# untitled.net
KiCad netlist of a schematic drawn in EAGLE
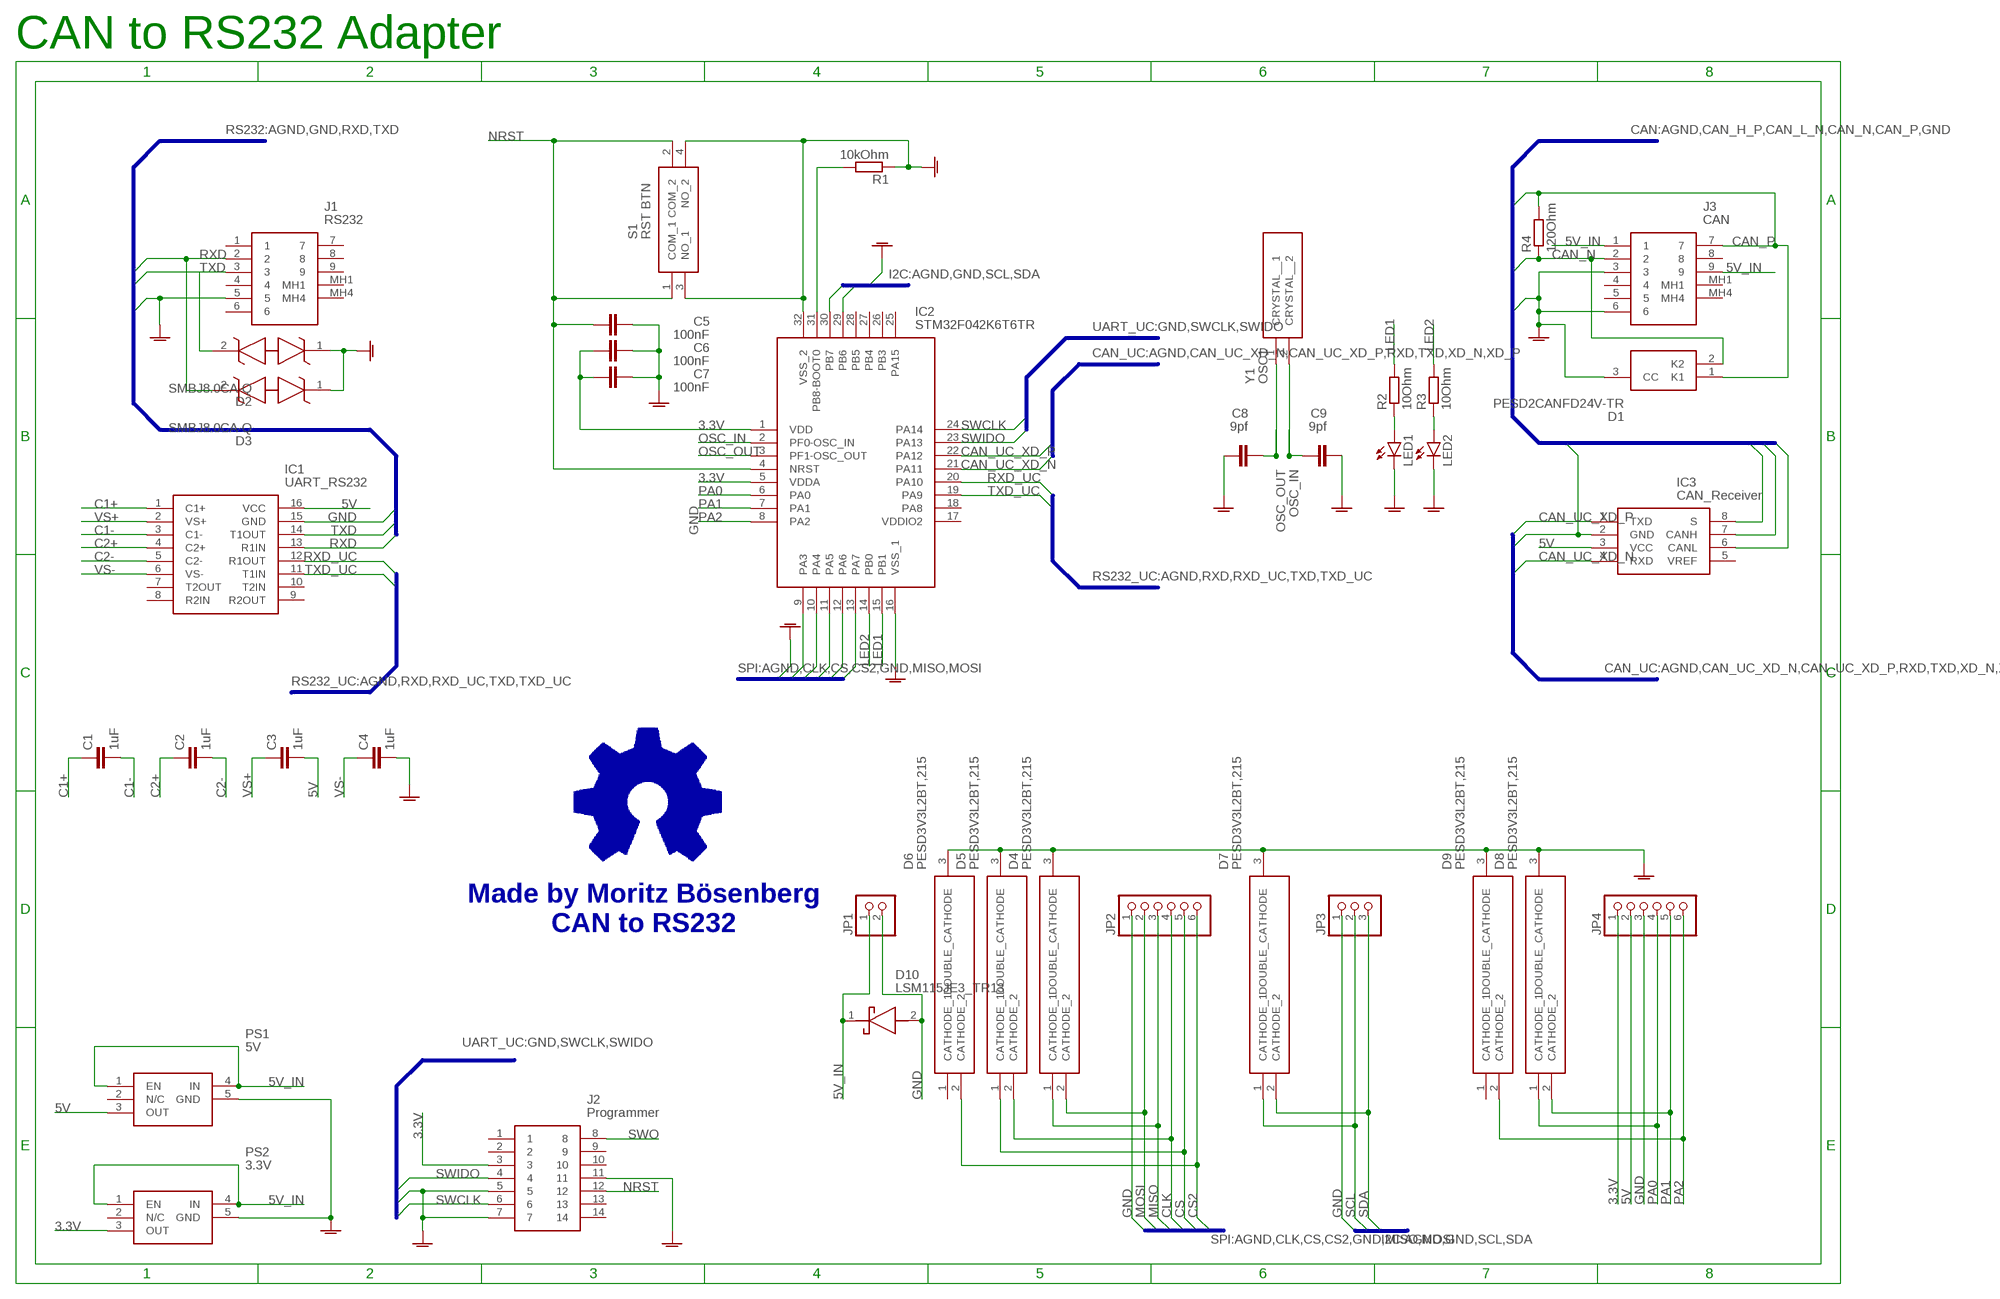
[diagram p0: schematic, sheet 1]

(export (version "E")
  (design (tool "Eeschema 10.0.6"))
  (components
    (comp (ref "C1")
      (value "1uF")
      (footprint "eagle-import:C0805")
      (libsource (lib "eagle-import") (part "C-EU_805C0805"))
    )
    (comp (ref "C2")
      (value "1uF")
      (footprint "eagle-import:C0805")
      (libsource (lib "eagle-import") (part "C-EU_805C0805"))
    )
    (comp (ref "C3")
      (value "1uF")
      (footprint "eagle-import:C0805")
      (libsource (lib "eagle-import") (part "C-EU_805C0805"))
    )
    (comp (ref "C4")
      (value "1uF")
      (footprint "eagle-import:C0805")
      (libsource (lib "eagle-import") (part "C-EU_805C0805"))
    )
    (comp (ref "C5")
      (value "100nF")
      (footprint "eagle-import:C0805")
      (libsource (lib "eagle-import") (part "C-EU_805C0805"))
    )
    (comp (ref "C6")
      (value "100nF")
      (footprint "eagle-import:C0805")
      (libsource (lib "eagle-import") (part "C-EU_805C0805"))
    )
    (comp (ref "C7")
      (value "100nF")
      (footprint "eagle-import:C0805")
      (libsource (lib "eagle-import") (part "C-EU_805C0805"))
    )
    (comp (ref "C8")
      (value "9pf")
      (footprint "eagle-import:C0805")
      (libsource (lib "eagle-import") (part "C-EU_805C0805"))
    )
    (comp (ref "C9")
      (value "9pf")
      (footprint "eagle-import:C0805")
      (libsource (lib "eagle-import") (part "C-EU_805C0805"))
    )
    (comp (ref "D1")
      (value "PESD2CANFD24V-TR")
      (footprint "eagle-import:SOT95P230X110-3N")
      (fields (field (name "MOUSER_PART_NUMBER") "771-PESD2CANFD24V-TR"))
      (libsource (lib "eagle-import") (part "PESD2CANFD24V-TR"))
    )
    (comp (ref "D2")
      (value "SMBJ8.0CA-Q")
      (footprint "eagle-import:DIONM5436X244N")
      (fields (field (name "MOUSER_PART_NUMBER") "652-SMBJ8.0CA-Q"))
      (libsource (lib "eagle-import") (part "SMBJ8.0CA-Q"))
    )
    (comp (ref "D3")
      (value "SMBJ8.0CA-Q")
      (footprint "eagle-import:DIONM5436X244N")
      (fields (field (name "MOUSER_PART_NUMBER") "652-SMBJ8.0CA-Q"))
      (libsource (lib "eagle-import") (part "SMBJ8.0CA-Q"))
    )
    (comp (ref "D4")
      (value "PESD3V3L2BT,215")
      (footprint "eagle-import:SOT95P230X110-3N")
      (fields (field (name "MOUSER_PART_NUMBER") "771-PESD3V3L2BT-T/R"))
      (libsource (lib "eagle-import") (part "PESD3V3L2BT,215"))
    )
    (comp (ref "D5")
      (value "PESD3V3L2BT,215")
      (footprint "eagle-import:SOT95P230X110-3N")
      (fields (field (name "MOUSER_PART_NUMBER") "771-PESD3V3L2BT-T/R"))
      (libsource (lib "eagle-import") (part "PESD3V3L2BT,215"))
    )
    (comp (ref "D6")
      (value "PESD3V3L2BT,215")
      (footprint "eagle-import:SOT95P230X110-3N")
      (fields (field (name "MOUSER_PART_NUMBER") "771-PESD3V3L2BT-T/R"))
      (libsource (lib "eagle-import") (part "PESD3V3L2BT,215"))
    )
    (comp (ref "D7")
      (value "PESD3V3L2BT,215")
      (footprint "eagle-import:SOT95P230X110-3N")
      (fields (field (name "MOUSER_PART_NUMBER") "771-PESD3V3L2BT-T/R"))
      (libsource (lib "eagle-import") (part "PESD3V3L2BT,215"))
    )
    (comp (ref "D8")
      (value "PESD3V3L2BT,215")
      (footprint "eagle-import:SOT95P230X110-3N")
      (fields (field (name "MOUSER_PART_NUMBER") "771-PESD3V3L2BT-T/R"))
      (libsource (lib "eagle-import") (part "PESD3V3L2BT,215"))
    )
    (comp (ref "D9")
      (value "PESD3V3L2BT,215")
      (footprint "eagle-import:SOT95P230X110-3N")
      (fields (field (name "MOUSER_PART_NUMBER") "771-PESD3V3L2BT-T/R"))
      (libsource (lib "eagle-import") (part "PESD3V3L2BT,215"))
    )
    (comp (ref "D10")
      (value "LSM115JE3_TR13")
      (footprint "eagle-import:DIOM5436X330N")
      (fields
        (field (name "MANUFACTURER_PART_NUMBER") "LSM115JE3/TR13")
        (field (name "MOUSER_PART_NUMBER") "494-LSM115JE3/TR13")
      )
      (libsource (lib "eagle-import") (part "LSM115JE3_TR13"))
    )
    (comp (ref "IC1")
      (value "UART_RS232")
      (footprint "eagle-import:SOIC127P600X175-16N")
      (fields
        (field (name "MANUFACTURER_PART_NUMBER") "MAX232DRG4")
        (field (name "MOUSER_PART_NUMBER") "595-MAX232DRG4")
      )
      (libsource (lib "eagle-import") (part "MAX232DRG4"))
    )
    (comp (ref "IC2")
      (value "STM32F042K6T6TR")
      (footprint "eagle-import:QFP80P900X900X160-32N")
      (fields (field (name "MOUSER_PART_NUMBER") "511-STM32F042K6T6TR"))
      (libsource (lib "eagle-import") (part "STM32F042K6T6TR"))
    )
    (comp (ref "IC3")
      (value "CAN_Receiver")
      (footprint "eagle-import:SOIC127P600X175-8N")
      (fields
        (field (name "MANUFACTURER_PART_NUMBER") "TJA1050T/CM,118")
        (field (name "MOUSER_PART_NUMBER") "771-TJA1050T/CM118")
      )
      (libsource (lib "eagle-import") (part "TJA1050T_CM,118"))
    )
    (comp (ref "J1")
      (value "RS232")
      (footprint "eagle-import:K202XHTE9SN")
      (fields
        (field (name "MANUFACTURER_PART_NUMBER") "K202XHT-E9S-N")
        (field (name "MOUSER_PART_NUMBER") "806-K202XHT-E9S-N")
      )
      (libsource (lib "eagle-import") (part "K202XHT-E9S-N"))
    )
    (comp (ref "J2")
      (value "Programmer")
      (footprint "eagle-import:FTSH10701LDVKA")
      (fields
        (field (name "MANUFACTURER_PART_NUMBER") "FTSH-107-01-L-DV-K-A")
        (field (name "MOUSER_PART_NUMBER") "200-FTSH10701LDVKA")
      )
      (libsource (lib "eagle-import") (part "FTSH-107-01-L-DV-K-A"))
    )
    (comp (ref "J3")
      (value "CAN")
      (footprint "eagle-import:K202XHTE9SN")
      (fields
        (field (name "MANUFACTURER_PART_NUMBER") "K202XHT-E9S-N")
        (field (name "MOUSER_PART_NUMBER") "806-K202XHT-E9S-N")
      )
      (libsource (lib "eagle-import") (part "K202XHT-E9S-N"))
    )
    (comp (ref "JP1")
      (value "PINHD-1X2")
      (footprint "eagle-import:1X02")
      (libsource (lib "eagle-import") (part "PINHD-1X2"))
    )
    (comp (ref "JP2")
      (value "PINHD-1X6")
      (footprint "eagle-import:1X06")
      (libsource (lib "eagle-import") (part "PINHD-1X6"))
    )
    (comp (ref "JP3")
      (value "PINHD-1X3")
      (footprint "eagle-import:1X03")
      (libsource (lib "eagle-import") (part "PINHD-1X3"))
    )
    (comp (ref "JP4")
      (value "PINHD-1X6")
      (footprint "eagle-import:1X06")
      (libsource (lib "eagle-import") (part "PINHD-1X6"))
    )
    (comp (ref "LED1")
      (value "LED_805SML0805")
      (footprint "eagle-import:SML0805")
      (libsource (lib "eagle-import") (part "LED_805SML0805"))
    )
    (comp (ref "LED2")
      (value "LED_805SML0805")
      (footprint "eagle-import:SML0805")
      (libsource (lib "eagle-import") (part "LED_805SML0805"))
    )
    (comp (ref "PS1")
      (value "5V")
      (footprint "eagle-import:SOT150P700X160-5N")
      (libsource (lib "eagle-import") (part "LP38693MPX-5.0_NOPB"))
    )
    (comp (ref "PS2")
      (value "3.3V")
      (footprint "eagle-import:SOT150P700X160-5N")
      (libsource (lib "eagle-import") (part "LP38693MPX-5.0_NOPB"))
    )
    (comp (ref "R1")
      (value "10kOhm")
      (footprint "eagle-import:R0805")
      (libsource (lib "eagle-import") (part "R-EU_805R0805"))
    )
    (comp (ref "R2")
      (value "10Ohm")
      (footprint "eagle-import:R0805")
      (libsource (lib "eagle-import") (part "R-EU_805R0805"))
    )
    (comp (ref "R3")
      (value "10Ohm")
      (footprint "eagle-import:R0805")
      (libsource (lib "eagle-import") (part "R-EU_805R0805"))
    )
    (comp (ref "R4")
      (value "120Ohm")
      (footprint "eagle-import:R0805")
      (libsource (lib "eagle-import") (part "R-EU_805R0805"))
    )
    (comp (ref "S1")
      (value "RST BTN")
      (footprint "eagle-import:PTS526SM15SMTR2LFS")
      (fields
        (field (name "MANUFACTURER_PART_NUMBER") "PTS526 SM15 SMTR2 LFS")
        (field (name "MOUSER_PART_NUMBER") "611-PTS526SM15SMTR2L")
      )
      (libsource (lib "eagle-import") (part "PTS526_SM15_SMTR2_LFS"))
    )
    (comp (ref "Y1")
      (value "OSC1")
      (footprint "eagle-import:CM7VT1A32768KHZ7PF100PPMTAQC")
      (fields
        (field (name "MANUFACTURER_PART_NUMBER") "CM7V-T1A-32.768KHZ-7PF-100PPM-TA-QC")
        (field (name "MOUSER_PART_NUMBER") "428-202156-MG01")
      )
      (libsource (lib "eagle-import") (part "CM7V-T1A-32.768KHZ-7PF-100PPM-"))
    )
  )
  (nets
    (net (code "12") (name "/3.3V") (class "Default")
      (node (ref "C6") (pin "1") (pinfunction "1_1") (pintype "passive"))
      (node (ref "C7") (pin "1") (pinfunction "1_1") (pintype "passive"))
      (node (ref "IC2") (pin "1") (pinfunction "VDD_1") (pintype "bidirectional"))
      (node (ref "IC2") (pin "5") (pinfunction "VDDA_5") (pintype "bidirectional"))
      (node (ref "J2") (pin "3") (pinfunction "3_3") (pintype "bidirectional"))
      (node (ref "JP4") (pin "1") (pinfunction "1_1") (pintype "passive"))
      (node (ref "PS2") (pin "3") (pinfunction "OUT_3") (pintype "bidirectional"))
    )
    (net (code "13") (name "/5V") (class "Default")
      (node (ref "C3") (pin "2") (pinfunction "2_2") (pintype "passive"))
      (node (ref "IC1") (pin "16") (pinfunction "VCC_16") (pintype "bidirectional"))
      (node (ref "IC3") (pin "3") (pinfunction "VCC_3") (pintype "bidirectional"))
      (node (ref "JP4") (pin "2") (pinfunction "2_2") (pintype "passive"))
      (node (ref "PS1") (pin "3") (pinfunction "OUT_3") (pintype "bidirectional"))
    )
    (net (code "14") (name "/5V_IN") (class "Default")
      (node (ref "D10") (pin "1") (pinfunction "K_1") (pintype "bidirectional"))
      (node (ref "J3") (pin "1") (pinfunction "1_1") (pintype "bidirectional"))
      (node (ref "J3") (pin "9") (pinfunction "9_9") (pintype "bidirectional"))
      (node (ref "JP1") (pin "1") (pinfunction "1_1") (pintype "passive"))
      (node (ref "PS1") (pin "1") (pinfunction "EN_1") (pintype "bidirectional"))
      (node (ref "PS1") (pin "4") (pinfunction "IN_4") (pintype "bidirectional"))
      (node (ref "PS2") (pin "1") (pinfunction "EN_1") (pintype "bidirectional"))
      (node (ref "PS2") (pin "4") (pinfunction "IN_4") (pintype "bidirectional"))
    )
    (net (code "15") (name "/C1+") (class "Default")
      (node (ref "C1") (pin "1") (pinfunction "1_1") (pintype "passive"))
      (node (ref "IC1") (pin "1") (pinfunction "C1+_1") (pintype "bidirectional"))
    )
    (net (code "16") (name "/C1-") (class "Default")
      (node (ref "C1") (pin "2") (pinfunction "2_2") (pintype "passive"))
      (node (ref "IC1") (pin "3") (pinfunction "C1-_3") (pintype "bidirectional"))
    )
    (net (code "17") (name "/C2+") (class "Default")
      (node (ref "C2") (pin "1") (pinfunction "1_1") (pintype "passive"))
      (node (ref "IC1") (pin "4") (pinfunction "C2+_4") (pintype "bidirectional"))
    )
    (net (code "18") (name "/C2-") (class "Default")
      (node (ref "C2") (pin "2") (pinfunction "2_2") (pintype "passive"))
      (node (ref "IC1") (pin "5") (pinfunction "C2-_5") (pintype "bidirectional"))
    )
    (net (code "19") (name "/CAN_N") (class "Default")
      (node (ref "D1") (pin "2") (pinfunction "K2_2") (pintype "bidirectional"))
      (node (ref "IC3") (pin "6") (pinfunction "CANL_6") (pintype "bidirectional"))
      (node (ref "J3") (pin "2") (pinfunction "2_2") (pintype "bidirectional"))
      (node (ref "R4") (pin "1") (pinfunction "1_1") (pintype "passive"))
    )
    (net (code "20") (name "/CAN_P") (class "Default")
      (node (ref "D1") (pin "1") (pinfunction "K1_1") (pintype "bidirectional"))
      (node (ref "IC3") (pin "7") (pinfunction "CANH_7") (pintype "bidirectional"))
      (node (ref "J3") (pin "7") (pinfunction "7_7") (pintype "bidirectional"))
      (node (ref "R4") (pin "2") (pinfunction "2_2") (pintype "passive"))
    )
    (net (code "21") (name "/CAN_UC_XD_N") (class "Default")
      (node (ref "IC2") (pin "21") (pinfunction "PA11_21") (pintype "bidirectional"))
      (node (ref "IC3") (pin "4") (pinfunction "RXD_4") (pintype "bidirectional"))
    )
    (net (code "22") (name "/CAN_UC_XD_P") (class "Default")
      (node (ref "IC2") (pin "22") (pinfunction "PA12_22") (pintype "bidirectional"))
      (node (ref "IC3") (pin "1") (pinfunction "TXD_1") (pintype "bidirectional"))
    )
    (net (code "23") (name "/CLK") (class "Default")
      (node (ref "D5") (pin "2") (pinfunction "CATHODE_2_2") (pintype "bidirectional"))
      (node (ref "IC2") (pin "11") (pinfunction "PA5_11") (pintype "bidirectional"))
      (node (ref "JP2") (pin "4") (pinfunction "4_4") (pintype "passive"))
    )
    (net (code "24") (name "/CS") (class "Default")
      (node (ref "D5") (pin "1") (pinfunction "CATHODE_1_1") (pintype "bidirectional"))
      (node (ref "IC2") (pin "10") (pinfunction "PA4_10") (pintype "bidirectional"))
      (node (ref "JP2") (pin "5") (pinfunction "5_5") (pintype "passive"))
    )
    (net (code "25") (name "/CS2") (class "Default")
      (node (ref "D6") (pin "2") (pinfunction "CATHODE_2_2") (pintype "bidirectional"))
      (node (ref "IC2") (pin "9") (pinfunction "PA3_9") (pintype "bidirectional"))
      (node (ref "JP2") (pin "6") (pinfunction "6_6") (pintype "passive"))
    )
    (net (code "26") (name "/LED1") (class "Default")
      (node (ref "IC2") (pin "15") (pinfunction "PB1_15") (pintype "bidirectional"))
      (node (ref "R2") (pin "2") (pinfunction "2_2") (pintype "passive"))
    )
    (net (code "27") (name "/LED2") (class "Default")
      (node (ref "IC2") (pin "14") (pinfunction "PB0_14") (pintype "bidirectional"))
      (node (ref "R3") (pin "2") (pinfunction "2_2") (pintype "passive"))
    )
    (net (code "28") (name "/MISO") (class "Default")
      (node (ref "D4") (pin "1") (pinfunction "CATHODE_1_1") (pintype "bidirectional"))
      (node (ref "IC2") (pin "12") (pinfunction "PA6_12") (pintype "bidirectional"))
      (node (ref "JP2") (pin "3") (pinfunction "3_3") (pintype "passive"))
    )
    (net (code "29") (name "/MOSI") (class "Default")
      (node (ref "D4") (pin "2") (pinfunction "CATHODE_2_2") (pintype "bidirectional"))
      (node (ref "IC2") (pin "13") (pinfunction "PA7_13") (pintype "bidirectional"))
      (node (ref "JP2") (pin "2") (pinfunction "2_2") (pintype "passive"))
    )
    (net (code "30") (name "/NRST") (class "Default")
      (node (ref "C5") (pin "1") (pinfunction "1_1") (pintype "passive"))
      (node (ref "IC2") (pin "4") (pinfunction "NRST_4") (pintype "bidirectional"))
      (node (ref "J2") (pin "12") (pinfunction "12_12") (pintype "bidirectional"))
      (node (ref "S1") (pin "1") (pinfunction "COM_1_1") (pintype "bidirectional"))
      (node (ref "S1") (pin "2") (pinfunction "COM_2_2") (pintype "bidirectional"))
    )
    (net (code "31") (name "/OSC_IN") (class "Default")
      (node (ref "C9") (pin "1") (pinfunction "1_1") (pintype "passive"))
      (node (ref "IC2") (pin "2") (pinfunction "PF0-OSC_IN_2") (pintype "bidirectional"))
      (node (ref "Y1") (pin "2") (pinfunction "CRYSTAL__2_2") (pintype "bidirectional"))
    )
    (net (code "32") (name "/OSC_OUT") (class "Default")
      (node (ref "C8") (pin "2") (pinfunction "2_2") (pintype "passive"))
      (node (ref "IC2") (pin "3") (pinfunction "PF1-OSC_OUT_3") (pintype "bidirectional"))
      (node (ref "Y1") (pin "1") (pinfunction "CRYSTAL__1_1") (pintype "bidirectional"))
    )
    (net (code "33") (name "/PA0") (class "Default")
      (node (ref "D8") (pin "1") (pinfunction "CATHODE_1_1") (pintype "bidirectional"))
      (node (ref "IC2") (pin "6") (pinfunction "PA0_6") (pintype "bidirectional"))
      (node (ref "JP4") (pin "4") (pinfunction "4_4") (pintype "passive"))
    )
    (net (code "34") (name "/PA1") (class "Default")
      (node (ref "D8") (pin "2") (pinfunction "CATHODE_2_2") (pintype "bidirectional"))
      (node (ref "IC2") (pin "7") (pinfunction "PA1_7") (pintype "bidirectional"))
      (node (ref "JP4") (pin "5") (pinfunction "5_5") (pintype "passive"))
    )
    (net (code "35") (name "/PA2") (class "Default")
      (node (ref "D9") (pin "2") (pinfunction "CATHODE_2_2") (pintype "bidirectional"))
      (node (ref "IC2") (pin "8") (pinfunction "PA2_8") (pintype "bidirectional"))
      (node (ref "JP4") (pin "6") (pinfunction "6_6") (pintype "passive"))
    )
    (net (code "36") (name "/RXD") (class "Default")
      (node (ref "D3") (pin "2") (pinfunction "2_2") (pintype "bidirectional"))
      (node (ref "IC1") (pin "13") (pinfunction "R1IN_13") (pintype "bidirectional"))
      (node (ref "J1") (pin "2") (pinfunction "2_2") (pintype "bidirectional"))
    )
    (net (code "37") (name "/RXD_UC") (class "Default")
      (node (ref "IC1") (pin "12") (pinfunction "R1OUT_12") (pintype "bidirectional"))
      (node (ref "IC2") (pin "20") (pinfunction "PA10_20") (pintype "bidirectional"))
    )
    (net (code "38") (name "/SCL") (class "Default")
      (node (ref "D7") (pin "1") (pinfunction "CATHODE_1_1") (pintype "bidirectional"))
      (node (ref "IC2") (pin "29") (pinfunction "PB6_29") (pintype "bidirectional"))
      (node (ref "JP3") (pin "2") (pinfunction "2_2") (pintype "passive"))
    )
    (net (code "39") (name "/SDA") (class "Default")
      (node (ref "D7") (pin "2") (pinfunction "CATHODE_2_2") (pintype "bidirectional"))
      (node (ref "IC2") (pin "30") (pinfunction "PB7_30") (pintype "bidirectional"))
      (node (ref "JP3") (pin "3") (pinfunction "3_3") (pintype "passive"))
    )
    (net (code "40") (name "/SWCLK") (class "Default")
      (node (ref "IC2") (pin "24") (pinfunction "PA14_24") (pintype "bidirectional"))
      (node (ref "J2") (pin "6") (pinfunction "6_6") (pintype "bidirectional"))
    )
    (net (code "41") (name "/SWIDO") (class "Default")
      (node (ref "IC2") (pin "23") (pinfunction "PA13_23") (pintype "bidirectional"))
      (node (ref "J2") (pin "4") (pinfunction "4_4") (pintype "bidirectional"))
    )
    (net (code "42") (name "/SWO") (class "Default")
      (node (ref "J2") (pin "8") (pinfunction "8_8") (pintype "bidirectional"))
    )
    (net (code "43") (name "/TXD") (class "Default")
      (node (ref "D2") (pin "2") (pinfunction "2_2") (pintype "bidirectional"))
      (node (ref "IC1") (pin "14") (pinfunction "T1OUT_14") (pintype "bidirectional"))
      (node (ref "J1") (pin "3") (pinfunction "3_3") (pintype "bidirectional"))
    )
    (net (code "44") (name "/TXD_UC") (class "Default")
      (node (ref "IC1") (pin "11") (pinfunction "T1IN_11") (pintype "bidirectional"))
      (node (ref "IC2") (pin "19") (pinfunction "PA9_19") (pintype "bidirectional"))
    )
    (net (code "45") (name "/VS+") (class "Default")
      (node (ref "C3") (pin "1") (pinfunction "1_1") (pintype "passive"))
      (node (ref "IC1") (pin "2") (pinfunction "VS+_2") (pintype "bidirectional"))
    )
    (net (code "46") (name "/VS-") (class "Default")
      (node (ref "C4") (pin "1") (pinfunction "1_1") (pintype "passive"))
      (node (ref "IC1") (pin "6") (pinfunction "VS-_6") (pintype "bidirectional"))
    )
    (net (code "54") (name "GNDA") (class "Default")
      (node (ref "C4") (pin "2") (pinfunction "2_2") (pintype "passive"))
      (node (ref "C5") (pin "2") (pinfunction "2_2") (pintype "passive"))
      (node (ref "C6") (pin "2") (pinfunction "2_2") (pintype "passive"))
      (node (ref "C7") (pin "2") (pinfunction "2_2") (pintype "passive"))
      (node (ref "C8") (pin "1") (pinfunction "1_1") (pintype "passive"))
      (node (ref "C9") (pin "2") (pinfunction "2_2") (pintype "passive"))
      (node (ref "D1") (pin "3") (pinfunction "CC_3") (pintype "bidirectional"))
      (node (ref "D10") (pin "2") (pinfunction "A_2") (pintype "bidirectional"))
      (node (ref "D2") (pin "1") (pinfunction "1_1") (pintype "bidirectional"))
      (node (ref "D3") (pin "1") (pinfunction "1_1") (pintype "bidirectional"))
      (node (ref "D4") (pin "3") (pinfunction "DOUBLE_CATHODE_3") (pintype "bidirectional"))
      (node (ref "D5") (pin "3") (pinfunction "DOUBLE_CATHODE_3") (pintype "bidirectional"))
      (node (ref "D6") (pin "3") (pinfunction "DOUBLE_CATHODE_3") (pintype "bidirectional"))
      (node (ref "D7") (pin "3") (pinfunction "DOUBLE_CATHODE_3") (pintype "bidirectional"))
      (node (ref "D8") (pin "3") (pinfunction "DOUBLE_CATHODE_3") (pintype "bidirectional"))
      (node (ref "D9") (pin "3") (pinfunction "DOUBLE_CATHODE_3") (pintype "bidirectional"))
      (node (ref "IC1") (pin "15") (pinfunction "GND_15") (pintype "bidirectional"))
      (node (ref "IC2") (pin "16") (pinfunction "VSS_1_16") (pintype "bidirectional"))
      (node (ref "IC2") (pin "32") (pinfunction "VSS_2_32") (pintype "bidirectional"))
      (node (ref "IC3") (pin "2") (pinfunction "GND_2") (pintype "bidirectional"))
      (node (ref "IC3") (pin "8") (pinfunction "S_8") (pintype "bidirectional"))
      (node (ref "J1") (pin "5") (pinfunction "5_5") (pintype "bidirectional"))
      (node (ref "J2") (pin "11") (pinfunction "11_11") (pintype "bidirectional"))
      (node (ref "J2") (pin "5") (pinfunction "5_5") (pintype "bidirectional"))
      (node (ref "J2") (pin "7") (pinfunction "7_7") (pintype "bidirectional"))
      (node (ref "J3") (pin "3") (pinfunction "3_3") (pintype "bidirectional"))
      (node (ref "J3") (pin "6") (pinfunction "6_6") (pintype "bidirectional"))
      (node (ref "JP1") (pin "2") (pinfunction "2_2") (pintype "passive"))
      (node (ref "JP2") (pin "1") (pinfunction "1_1") (pintype "passive"))
      (node (ref "JP3") (pin "1") (pinfunction "1_1") (pintype "passive"))
      (node (ref "JP4") (pin "3") (pinfunction "3_3") (pintype "passive"))
      (node (ref "LED1") (pin "C") (pinfunction "C_C") (pintype "passive"))
      (node (ref "LED2") (pin "C") (pinfunction "C_C") (pintype "passive"))
      (node (ref "PS1") (pin "5") (pinfunction "GND_5") (pintype "bidirectional"))
      (node (ref "PS2") (pin "5") (pinfunction "GND_5") (pintype "bidirectional"))
      (node (ref "R1") (pin "1") (pinfunction "1_1") (pintype "passive"))
      (node (ref "S1") (pin "3") (pinfunction "NO_1_3") (pintype "bidirectional"))
      (node (ref "S1") (pin "4") (pinfunction "NO_2_4") (pintype "bidirectional"))
    )
    (net (code "55") (name "Net-(IC2-PB8-BOOT0)") (class "Default")
      (node (ref "IC2") (pin "31") (pinfunction "PB8-BOOT0_31") (pintype "bidirectional"))
      (node (ref "R1") (pin "2") (pinfunction "2_2") (pintype "passive"))
    )
    (net (code "56") (name "Net-(LED1-PadA)") (class "Default")
      (node (ref "LED1") (pin "A") (pinfunction "A_A") (pintype "passive"))
      (node (ref "R2") (pin "1") (pinfunction "1_1") (pintype "passive"))
    )
    (net (code "57") (name "Net-(LED2-PadA)") (class "Default")
      (node (ref "LED2") (pin "A") (pinfunction "A_A") (pintype "passive"))
      (node (ref "R3") (pin "1") (pinfunction "1_1") (pintype "passive"))
    )
    (net (code "58") (name "unconnected-(D6-CATHODE_1-Pad1)") (class "Default")
      (node (ref "D6") (pin "1") (pinfunction "CATHODE_1_1") (pintype "bidirectional"))
    )
    (net (code "59") (name "unconnected-(D9-CATHODE_1-Pad1)") (class "Default")
      (node (ref "D9") (pin "1") (pinfunction "CATHODE_1_1") (pintype "bidirectional"))
    )
    (net (code "60") (name "unconnected-(IC1-R2IN-Pad8)") (class "Default")
      (node (ref "IC1") (pin "8") (pinfunction "R2IN_8") (pintype "bidirectional"))
    )
    (net (code "61") (name "unconnected-(IC1-R2OUT-Pad9)") (class "Default")
      (node (ref "IC1") (pin "9") (pinfunction "R2OUT_9") (pintype "bidirectional"))
    )
    (net (code "62") (name "unconnected-(IC1-T2IN-Pad10)") (class "Default")
      (node (ref "IC1") (pin "10") (pinfunction "T2IN_10") (pintype "bidirectional"))
    )
    (net (code "63") (name "unconnected-(IC1-T2OUT-Pad7)") (class "Default")
      (node (ref "IC1") (pin "7") (pinfunction "T2OUT_7") (pintype "bidirectional"))
    )
    (net (code "64") (name "unconnected-(IC2-PA8-Pad18)") (class "Default")
      (node (ref "IC2") (pin "18") (pinfunction "PA8_18") (pintype "bidirectional"))
    )
    (net (code "65") (name "unconnected-(IC2-PA15-Pad25)") (class "Default")
      (node (ref "IC2") (pin "25") (pinfunction "PA15_25") (pintype "bidirectional"))
    )
    (net (code "66") (name "unconnected-(IC2-PB3-Pad26)") (class "Default")
      (node (ref "IC2") (pin "26") (pinfunction "PB3_26") (pintype "bidirectional"))
    )
    (net (code "67") (name "unconnected-(IC2-PB4-Pad27)") (class "Default")
      (node (ref "IC2") (pin "27") (pinfunction "PB4_27") (pintype "bidirectional"))
    )
    (net (code "68") (name "unconnected-(IC2-PB5-Pad28)") (class "Default")
      (node (ref "IC2") (pin "28") (pinfunction "PB5_28") (pintype "bidirectional"))
    )
    (net (code "69") (name "unconnected-(IC2-VDDIO2-Pad17)") (class "Default")
      (node (ref "IC2") (pin "17") (pinfunction "VDDIO2_17") (pintype "bidirectional"))
    )
    (net (code "70") (name "unconnected-(IC3-VREF-Pad5)") (class "Default")
      (node (ref "IC3") (pin "5") (pinfunction "VREF_5") (pintype "bidirectional"))
    )
    (net (code "71") (name "unconnected-(J1-Pad1)") (class "Default")
      (node (ref "J1") (pin "1") (pinfunction "1_1") (pintype "bidirectional"))
    )
    (net (code "72") (name "unconnected-(J1-Pad4)") (class "Default")
      (node (ref "J1") (pin "4") (pinfunction "4_4") (pintype "bidirectional"))
    )
    (net (code "73") (name "unconnected-(J1-Pad6)") (class "Default")
      (node (ref "J1") (pin "6") (pinfunction "6_6") (pintype "bidirectional"))
    )
    (net (code "74") (name "unconnected-(J1-Pad7)") (class "Default")
      (node (ref "J1") (pin "7") (pinfunction "7_7") (pintype "bidirectional"))
    )
    (net (code "75") (name "unconnected-(J1-Pad8)") (class "Default")
      (node (ref "J1") (pin "8") (pinfunction "8_8") (pintype "bidirectional"))
    )
    (net (code "76") (name "unconnected-(J1-Pad9)") (class "Default")
      (node (ref "J1") (pin "9") (pinfunction "9_9") (pintype "bidirectional"))
    )
    (net (code "77") (name "unconnected-(J1-PadMH1)") (class "Default")
      (node (ref "J1") (pin "MH1") (pinfunction "MH1_MH1") (pintype "bidirectional"))
    )
    (net (code "78") (name "unconnected-(J1-PadMH4)") (class "Default")
      (node (ref "J1") (pin "MH4") (pinfunction "MH4_MH4") (pintype "bidirectional"))
    )
    (net (code "79") (name "unconnected-(J2-Pad1)") (class "Default")
      (node (ref "J2") (pin "1") (pinfunction "1_1") (pintype "bidirectional"))
    )
    (net (code "80") (name "unconnected-(J2-Pad2)") (class "Default")
      (node (ref "J2") (pin "2") (pinfunction "2_2") (pintype "bidirectional"))
    )
    (net (code "81") (name "unconnected-(J2-Pad9)") (class "Default")
      (node (ref "J2") (pin "9") (pinfunction "9_9") (pintype "bidirectional"))
    )
    (net (code "82") (name "unconnected-(J2-Pad10)") (class "Default")
      (node (ref "J2") (pin "10") (pinfunction "10_10") (pintype "bidirectional"))
    )
    (net (code "83") (name "unconnected-(J2-Pad13)") (class "Default")
      (node (ref "J2") (pin "13") (pinfunction "13_13") (pintype "bidirectional"))
    )
    (net (code "84") (name "unconnected-(J2-Pad14)") (class "Default")
      (node (ref "J2") (pin "14") (pinfunction "14_14") (pintype "bidirectional"))
    )
    (net (code "85") (name "unconnected-(J3-Pad4)") (class "Default")
      (node (ref "J3") (pin "4") (pinfunction "4_4") (pintype "bidirectional"))
    )
    (net (code "86") (name "unconnected-(J3-Pad5)") (class "Default")
      (node (ref "J3") (pin "5") (pinfunction "5_5") (pintype "bidirectional"))
    )
    (net (code "87") (name "unconnected-(J3-Pad8)") (class "Default")
      (node (ref "J3") (pin "8") (pinfunction "8_8") (pintype "bidirectional"))
    )
    (net (code "88") (name "unconnected-(J3-PadMH1)") (class "Default")
      (node (ref "J3") (pin "MH1") (pinfunction "MH1_MH1") (pintype "bidirectional"))
    )
    (net (code "89") (name "unconnected-(J3-PadMH4)") (class "Default")
      (node (ref "J3") (pin "MH4") (pinfunction "MH4_MH4") (pintype "bidirectional"))
    )
    (net (code "90") (name "unconnected-(PS1-N{slash}C-Pad2)") (class "Default")
      (node (ref "PS1") (pin "2") (pinfunction "N/C_2") (pintype "no_connect"))
    )
    (net (code "91") (name "unconnected-(PS2-N{slash}C-Pad2)") (class "Default")
      (node (ref "PS2") (pin "2") (pinfunction "N/C_2") (pintype "no_connect"))
    )
  )
)
